# PWRBankCharger.net
KiCad netlist of a schematic drawn in Altium Designer
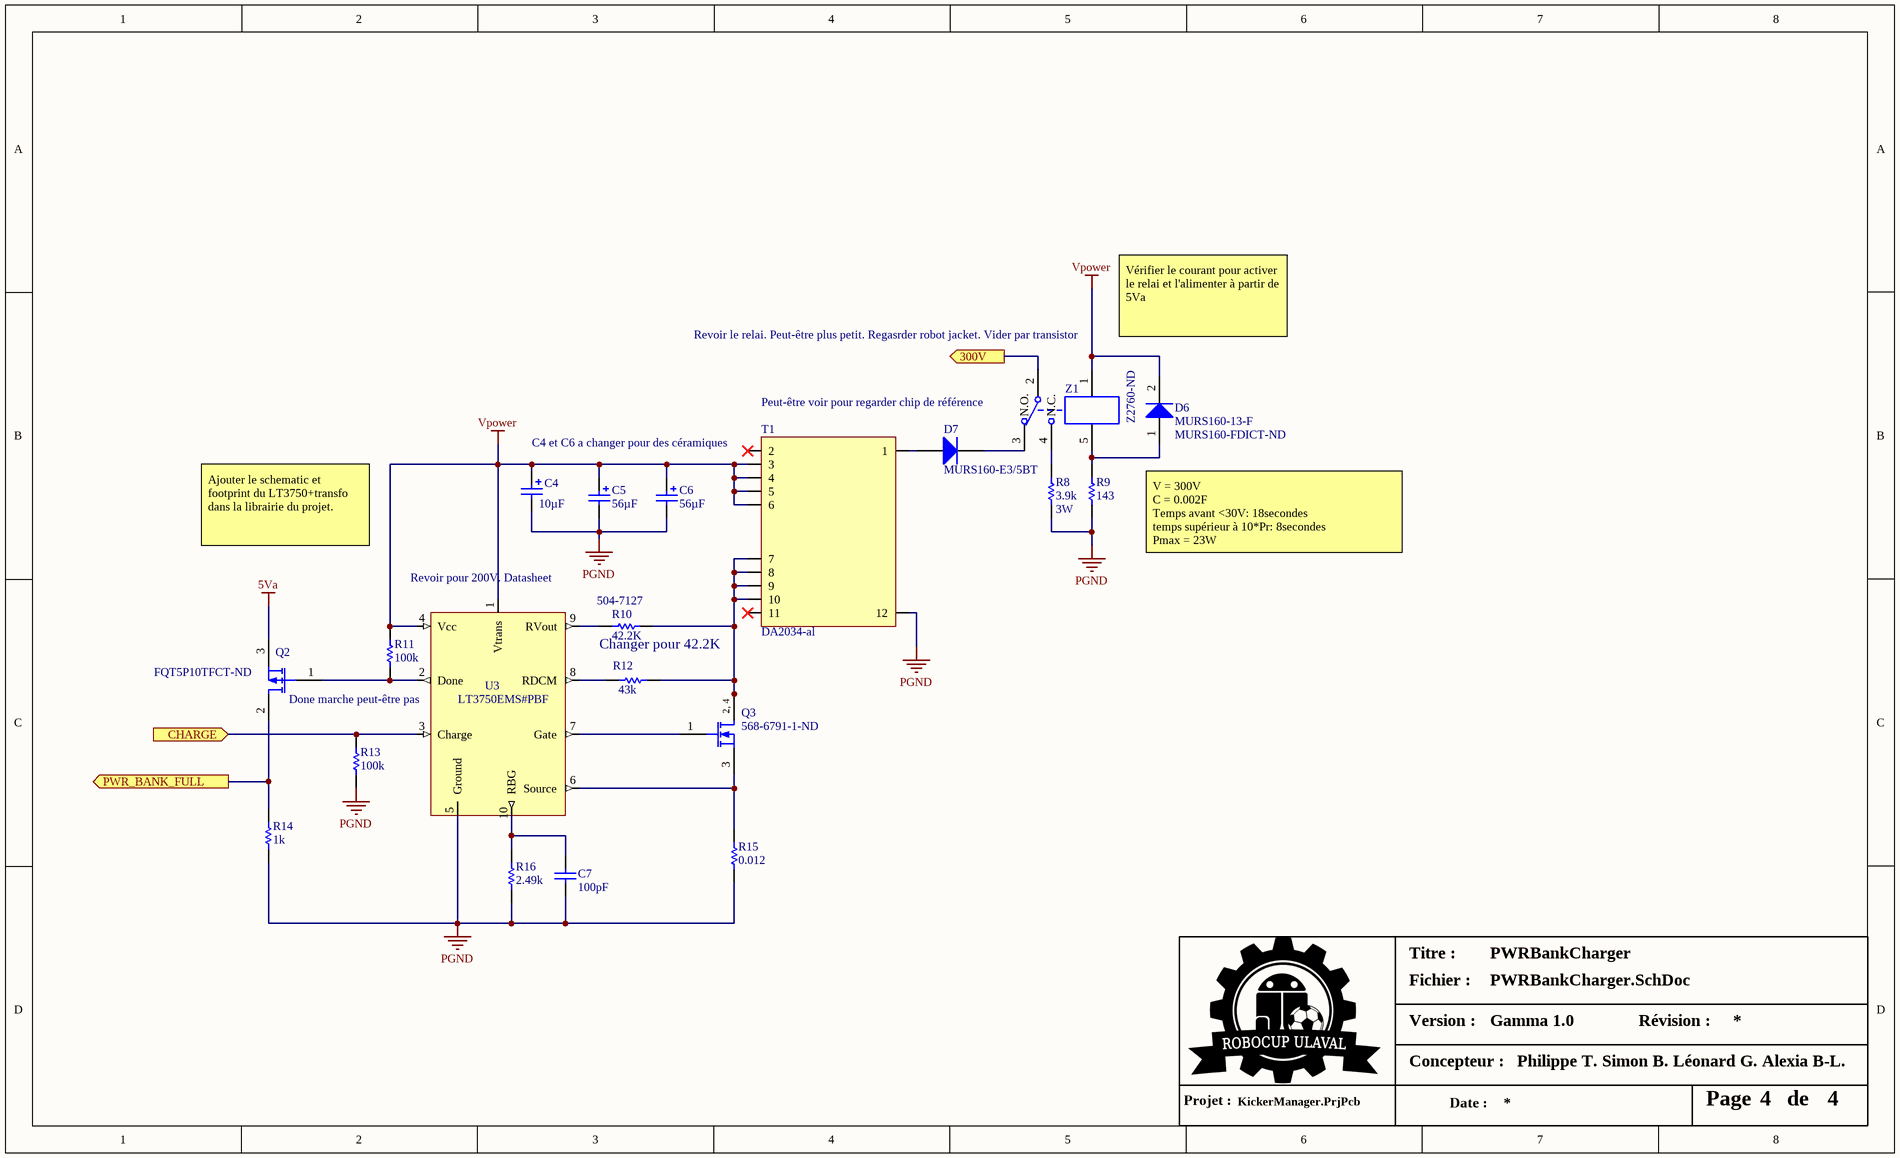
[diagram p0: PWRBankCharger.SchDoc]

(export (version "E")
  (design (tool "Eeschema 10.0.6"))
  (components
    (comp (ref "C4")
      (value "865230340001")
      (footprint "CAP 4.3x4.3mm")
      (description "CAP 10 UF 20% 16 V")
      (fields
        (field (name "MANUFACTURER") "Wurth Electronics Inc")
        (field (name "CAPACITANCE") "10µF")
        (field (name "TOLERANCE") "±20%")
      )
      (libsource (lib "ResCap") (part "865230340001"))
    )
    (comp (ref "C5")
      (value "865080545010")
      (footprint "CAP 6.6x6.6mm")
      (description "CAP 56 UF 20% 35 V")
      (fields
        (field (name "MANUFACTURER") "Wurth Electronics Inc")
        (field (name "TOLERANCE") "±20%")
        (field (name "CAPACITANCE") "56µF")
      )
      (libsource (lib "ResCap") (part "865080545010"))
    )
    (comp (ref "C6")
      (value "865080545010")
      (footprint "CAP 6.6x6.6mm")
      (description "CAP 56 UF 20% 35 V")
      (fields
        (field (name "MANUFACTURER") "Wurth Electronics Inc")
        (field (name "TOLERANCE") "±20%")
        (field (name "CAPACITANCE") "56µF")
      )
      (libsource (lib "ResCap") (part "865080545010"))
    )
    (comp (ref "C7")
      (value "CL10B101KB8NNNC")
      (footprint "0603")
      (description "CAP CER 100PF 50V X7R 0603")
      (fields
        (field (name "MANUFACTURER") "Samsung Electro-Mechanics America, Inc.")
        (field (name "TOLERANCE") "±10%")
        (field (name "CAPACITANCE") "100pF")
      )
      (libsource (lib "ResCap") (part "CL10B101KB8NNNC"))
    )
    (comp (ref "D6")
      (value "MURS160-13-F")
      (footprint "SMB")
      (description "DIODE GEN PURP 600V 1A SMB")
      (fields
        (field (name "MANUFACTURER") "Diodes Incorporated")
        (field (name "SUPPLIER PART NUMBER 1") "MURS160-FDICT-ND")
      )
      (libsource (lib "gamma_gestionkicker") (part "MURS160-13-F"))
    )
    (comp (ref "D7")
      (value "MURS160-E3/5BT")
      (footprint "SMB")
      (description "DIODE GEN PURP 600V 2A DO214AA")
      (fields (field (name "MANUFACTURER") "Vishay Semiconductor Diodes Division"))
      (libsource (lib "gamma_gestionkicker") (part "MURS160-E3/5BT"))
    )
    (comp (ref "Q2")
      (value "FQT5P10TF")
      (footprint "SOT-223")
      (description "MOSFET P-CH 100V 1A SOT-223")
      (fields
        (field (name "MANUFACTURER") "Fairchild Semiconductor")
        (field (name "SUPPLIER PART NUMBER 1") "FQT5P10TFCT-ND")
      )
      (libsource (lib "gamma_gestionkicker") (part "FQT5P10TF"))
    )
    (comp (ref "Q3")
      (value "PHT6NQ10T,135")
      (footprint "SOT-223")
      (description "MOSFET N-CH 100V 3A SOT223")
      (fields
        (field (name "MANUFACTURER") "NXP Semiconductors")
        (field (name "SUPPLIER PART NUMBER 1") "568-6791-1-ND")
      )
      (libsource (lib "gamma_gestionkicker") (part "PHT6NQ10T,135"))
    )
    (comp (ref "R8")
      (value "RWM04103901JR15E1")
      (footprint "RWM4x10")
      (description "RES WIREWOUND 3.9K OHM 3W")
      (fields
        (field (name "MANUFACTURER") "Vishay Sfernice")
        (field (name "TOLERANCE") "±5%")
        (field (name "RESISTANCE (OHMS)") "3.9k")
        (field (name "POWER (WATTS)") "3W")
      )
      (libsource (lib "gamma_gestionkicker") (part "RWM04103901JR15E1"))
    )
    (comp (ref "R9")
      (value "CRCW1206143RFKEA")
      (footprint "1206")
      (description "RES SMD 143 OHM 1% 1/4W 1206")
      (fields
        (field (name "MANUFACTURER") "Vishay Dale")
        (field (name "TOLERANCE") "±1%")
        (field (name "RESISTANCE (OHMS)") "143")
      )
      (libsource (lib "ResCap") (part "CRCW1206143RFKEA"))
    )
    (comp (ref "R10")
      (value "RC0603FR-0742K2L")
      (footprint "0603")
      (description "RES SMD 42.2K OHM 1% 1/10W 0603")
      (fields
        (field (name "MANUFACTURER") "Yageo")
        (field (name "MANUFACTURER PART NUMBER") "RC0603FR-0760K4L")
        (field (name "RESISTANCE (OHMS)") "42.2K")
        (field (name "SUPPLIER PART NUMBER 1") "504-7127")
      )
      (libsource (lib "ResCap") (part "RC0603FR-0760K4L"))
    )
    (comp (ref "R11")
      (value "RC0603JR-07100KL")
      (footprint "0603")
      (description "RES SMD 100K OHM 5% 1/10W 0603")
      (fields
        (field (name "MANUFACTURER") "Yageo")
        (field (name "TOLERANCE") "±5%")
        (field (name "RESISTANCE (OHMS)") "100k")
      )
      (libsource (lib "ResCap") (part "RC0603JR-07100KL"))
    )
    (comp (ref "R12")
      (value "RC0603JR-0743KL")
      (footprint "0603")
      (description "RES SMD 43K OHM 5% 1/10W 0603")
      (fields
        (field (name "MANUFACTURER") "Yageo")
        (field (name "TOLERANCE") "±5%")
        (field (name "RESISTANCE (OHMS)") "43k")
      )
      (libsource (lib "ResCap") (part "RC0603JR-0743KL"))
    )
    (comp (ref "R13")
      (value "RC0603JR-07100KL")
      (footprint "0603")
      (description "RES SMD 100K OHM 5% 1/10W 0603")
      (fields
        (field (name "MANUFACTURER") "Yageo")
        (field (name "TOLERANCE") "±5%")
        (field (name "RESISTANCE (OHMS)") "100k")
      )
      (libsource (lib "ResCap") (part "RC0603JR-07100KL"))
    )
    (comp (ref "R14")
      (value "RC0603JR-071KL")
      (footprint "0603")
      (description "RES SMD 1K OHM 5% 1/10W 0603")
      (fields
        (field (name "MANUFACTURER") "Yageo")
        (field (name "TOLERANCE") "±5%")
        (field (name "RESISTANCE (OHMS)") "1k")
      )
      (libsource (lib "ResCap") (part "RC0603JR-071KL"))
    )
    (comp (ref "R15")
      (value "RL1220T-R012-J")
      (footprint "0805")
      (description "RES SMD 0.012 OHM 5% 1/4W 0805")
      (fields
        (field (name "MANUFACTURER") "Susumu")
        (field (name "TOLERANCE") "±5%")
        (field (name "RESISTANCE (OHMS)") "0.012")
      )
      (libsource (lib "ResCap") (part "RL1220T-R012-J"))
    )
    (comp (ref "R16")
      (value "RC0603FR-072K49L")
      (footprint "0603")
      (description "RES SMD 2.49K OHM 1% 1/10W 0603")
      (fields
        (field (name "MANUFACTURER") "Yageo")
        (field (name "TOLERANCE") "±1%")
        (field (name "RESISTANCE (OHMS)") "2.49k")
      )
      (libsource (lib "ResCap") (part "RC0603FR-072K49L"))
    )
    (comp (ref "T1")
      (value "DA2034-al")
      (footprint "da2034")
      (libsource (lib "da2034-al") (part "DA2034-al"))
    )
    (comp (ref "U3")
      (value "LT3750EMS#PBF")
      (footprint "MSOP-10")
      (description "IC CONVERTER 10-MSOP")
      (fields (field (name "MANUFACTURER") "Linear Technology"))
      (libsource (lib "gamma_gestionkicker") (part "LT3750EMS#PBF"))
    )
    (comp (ref "Z1")
      (value "G6RL-1 DC12")
      (footprint "G6RL")
      (description "RELAY GEN PURPOSE SPDT 8A 12V")
      (fields
        (field (name "MANUFACTURER") "Omron Electronics Inc-EMC Div")
        (field (name "SUPPLIER PART NUMBER 1") "Z2760-ND")
      )
      (libsource (lib "gamma_gestionkicker") (part "G6RL-1 DC12"))
    )
  )
  (nets
    (net (code "1") (name "/300V") (class "Default")
      (node (ref "Z1") (pin "2") (pinfunction "Signal_Input_2") (pintype "passive"))
    )
    (net (code "2") (name "/CHARGE") (class "Default")
      (node (ref "R13") (pin "2") (pinfunction "2_2") (pintype "passive"))
      (node (ref "U3") (pin "3") (pinfunction "Charge_3") (pintype "input"))
    )
    (net (code "3") (name "/PWR_BANK_FULL") (class "Default")
      (node (ref "Q2") (pin "2") (pinfunction "D_2") (pintype "passive"))
      (node (ref "R14") (pin "2") (pinfunction "2_2") (pintype "passive"))
    )
    (net (code "4") (name "5Va") (class "Default")
      (node (ref "Q2") (pin "3") (pinfunction "S_3") (pintype "passive"))
    )
    (net (code "5") (name "Net-(D6-A)") (class "Default")
      (node (ref "D6") (pin "1") (pinfunction "A_1") (pintype "passive"))
      (node (ref "R9") (pin "1") (pinfunction "1_1") (pintype "passive"))
      (node (ref "Z1") (pin "5") (pinfunction "Coil_Input_-_5") (pintype "passive"))
    )
    (net (code "6") (name "Net-(D7-A)") (class "Default")
      (node (ref "D7") (pin "1") (pinfunction "A_1") (pintype "passive"))
      (node (ref "T1") (pin "1") (pinfunction "1_1") (pintype "passive"))
    )
    (net (code "7") (name "Net-(D7-K)") (class "Default")
      (node (ref "D7") (pin "2") (pinfunction "K_2") (pintype "passive"))
      (node (ref "Z1") (pin "3") (pinfunction "N.O._3") (pintype "passive"))
    )
    (net (code "8") (name "Net-(Q2-G)") (class "Default")
      (node (ref "Q2") (pin "1") (pinfunction "G_1") (pintype "passive"))
      (node (ref "R11") (pin "1") (pinfunction "1_1") (pintype "passive"))
      (node (ref "U3") (pin "2") (pinfunction "Done_2") (pintype "output"))
    )
    (net (code "9") (name "Net-(Q3-D-Pad2)") (class "Default")
      (node (ref "Q3") (pin "2") (pinfunction "D_2") (pintype "passive"))
      (node (ref "Q3") (pin "4") (pinfunction "D_4") (pintype "passive"))
      (node (ref "R10") (pin "2") (pinfunction "2_2") (pintype "passive"))
      (node (ref "R12") (pin "1") (pinfunction "1_1") (pintype "passive"))
      (node (ref "T1") (pin "10") (pinfunction "10_10") (pintype "passive"))
      (node (ref "T1") (pin "7") (pinfunction "7_7") (pintype "passive"))
      (node (ref "T1") (pin "8") (pinfunction "8_8") (pintype "passive"))
      (node (ref "T1") (pin "9") (pinfunction "9_9") (pintype "passive"))
    )
    (net (code "10") (name "Net-(Q3-G)") (class "Default")
      (node (ref "Q3") (pin "1") (pinfunction "G_1") (pintype "passive"))
      (node (ref "U3") (pin "7") (pinfunction "Gate_7") (pintype "output"))
    )
    (net (code "11") (name "Net-(Q3-S)") (class "Default")
      (node (ref "Q3") (pin "3") (pinfunction "S_3") (pintype "passive"))
      (node (ref "R15") (pin "2") (pinfunction "2_2") (pintype "passive"))
      (node (ref "U3") (pin "6") (pinfunction "Source_6") (pintype "output"))
    )
    (net (code "12") (name "Net-(U3-RBG)") (class "Default")
      (node (ref "C7") (pin "1") (pinfunction "1_1") (pintype "passive"))
      (node (ref "R16") (pin "2") (pinfunction "2_2") (pintype "passive"))
      (node (ref "U3") (pin "10") (pinfunction "RBG_10") (pintype "output"))
    )
    (net (code "13") (name "Net-(U3-RDCM)") (class "Default")
      (node (ref "R12") (pin "2") (pinfunction "2_2") (pintype "passive"))
      (node (ref "U3") (pin "8") (pinfunction "RDCM_8") (pintype "output"))
    )
    (net (code "14") (name "Net-(U3-RVout)") (class "Default")
      (node (ref "R10") (pin "1") (pinfunction "1_1") (pintype "passive"))
      (node (ref "U3") (pin "9") (pinfunction "RVout_9") (pintype "output"))
    )
    (net (code "15") (name "Net-(Z1-N.C.)") (class "Default")
      (node (ref "R8") (pin "2") (pinfunction "2_2") (pintype "passive"))
      (node (ref "Z1") (pin "4") (pinfunction "N.C._4") (pintype "passive"))
    )
    (net (code "16") (name "PGND") (class "Default")
      (node (ref "C4") (pin "2") (pinfunction "2_2") (pintype "passive"))
      (node (ref "C5") (pin "2") (pinfunction "2_2") (pintype "passive"))
      (node (ref "C6") (pin "2") (pinfunction "2_2") (pintype "passive"))
      (node (ref "C7") (pin "2") (pinfunction "2_2") (pintype "passive"))
      (node (ref "R13") (pin "1") (pinfunction "1_1") (pintype "passive"))
      (node (ref "R14") (pin "1") (pinfunction "1_1") (pintype "passive"))
      (node (ref "R15") (pin "1") (pinfunction "1_1") (pintype "passive"))
      (node (ref "R16") (pin "1") (pinfunction "1_1") (pintype "passive"))
      (node (ref "R8") (pin "1") (pinfunction "1_1") (pintype "passive"))
      (node (ref "R9") (pin "2") (pinfunction "2_2") (pintype "passive"))
      (node (ref "T1") (pin "12") (pinfunction "12_12") (pintype "passive"))
      (node (ref "U3") (pin "5") (pinfunction "Ground_5") (pintype "power_in"))
    )
    (net (code "17") (name "Vpower") (class "Default")
      (node (ref "C4") (pin "1") (pinfunction "1_1") (pintype "passive"))
      (node (ref "C5") (pin "1") (pinfunction "1_1") (pintype "passive"))
      (node (ref "C6") (pin "1") (pinfunction "1_1") (pintype "passive"))
      (node (ref "D6") (pin "2") (pinfunction "K_2") (pintype "passive"))
      (node (ref "R11") (pin "2") (pinfunction "2_2") (pintype "passive"))
      (node (ref "T1") (pin "3") (pinfunction "3_3") (pintype "passive"))
      (node (ref "T1") (pin "4") (pinfunction "4_4") (pintype "passive"))
      (node (ref "T1") (pin "5") (pinfunction "5_5") (pintype "passive"))
      (node (ref "T1") (pin "6") (pinfunction "6_6") (pintype "passive"))
      (node (ref "U3") (pin "1") (pinfunction "Vtrans_1") (pintype "bidirectional"))
      (node (ref "U3") (pin "4") (pinfunction "Vcc_4") (pintype "input"))
      (node (ref "Z1") (pin "1") (pinfunction "Coil_Input_+_1") (pintype "passive"))
    )
    (net (code "18") (name "unconnected-(T1-Pad2)") (class "Default")
      (node (ref "T1") (pin "2") (pinfunction "2_2") (pintype "passive+no_connect"))
    )
    (net (code "19") (name "unconnected-(T1-Pad11)") (class "Default")
      (node (ref "T1") (pin "11") (pinfunction "11_11") (pintype "passive+no_connect"))
    )
  )
)
